# ramboard.net
KiCad netlist of a schematic drawn in EAGLE
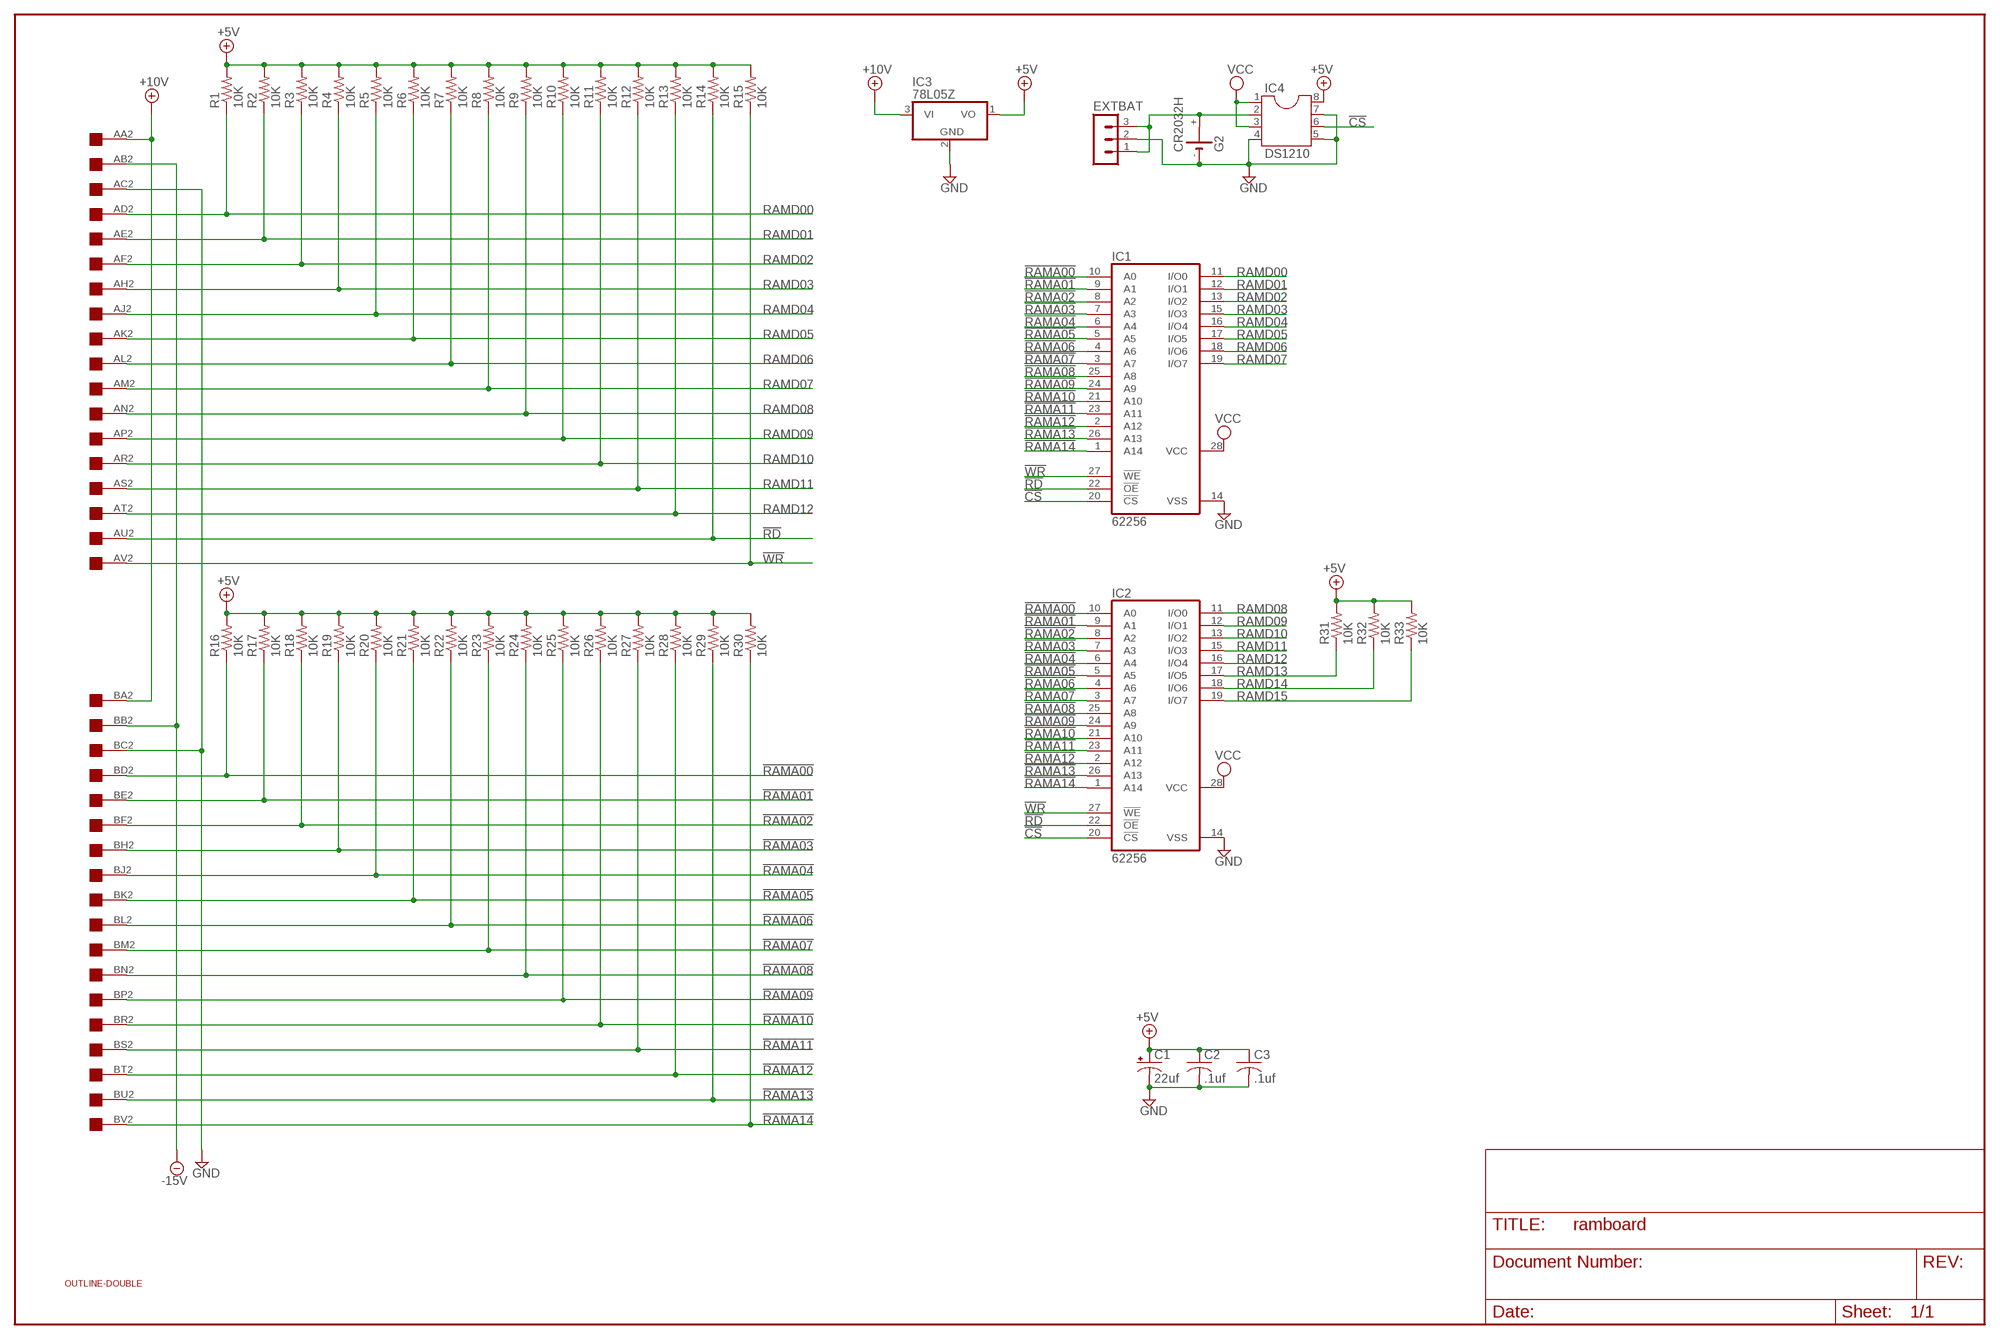
[diagram p0: schematic, sheet 1]

(export (version "E")
  (design (tool "Eeschema 10.0.6"))
  (components
    (comp (ref "C1")
      (value "22uf")
      (footprint "eagle-import:E22-6")
      (libsource (lib "eagle-import") (part "CPOL-USE22-6AXIAL"))
    )
    (comp (ref "C2")
      (value ".1uf")
      (footprint "eagle-import:C050-025X075")
      (libsource (lib "eagle-import") (part "C-US050-025X075"))
    )
    (comp (ref "C3")
      (value ".1uf")
      (footprint "eagle-import:C050-025X075")
      (libsource (lib "eagle-import") (part "C-US050-025X075"))
    )
    (comp (ref "EXTBAT")
      (value "MA03-1")
      (footprint "eagle-import:MA03-1")
      (libsource (lib "eagle-import") (part "MA03-1"))
    )
    (comp (ref "G2")
      (value "CR2032H")
      (footprint "eagle-import:CR2032H")
      (libsource (lib "eagle-import") (part "CR2032H"))
    )
    (comp (ref "IC1")
      (value "62256")
      (footprint "eagle-import:DIL28-6")
      (libsource (lib "eagle-import") (part "62256P"))
    )
    (comp (ref "IC2")
      (value "62256")
      (footprint "eagle-import:DIL28-6")
      (libsource (lib "eagle-import") (part "62256P"))
    )
    (comp (ref "IC3")
      (value "78L05Z")
      (footprint "eagle-import:TO92")
      (libsource (lib "eagle-import") (part "78ZL05"))
    )
    (comp (ref "IC4")
      (value "DS1210")
      (footprint "eagle-import:SOCKET-08")
      (libsource (lib "eagle-import") (part "DIL8S"))
    )
    (comp (ref "R1")
      (value "10K")
      (footprint "eagle-import:0207_10")
      (libsource (lib "eagle-import") (part "R-US_0207/10"))
    )
    (comp (ref "R2")
      (value "10K")
      (footprint "eagle-import:0207_10")
      (libsource (lib "eagle-import") (part "R-US_0207/10"))
    )
    (comp (ref "R3")
      (value "10K")
      (footprint "eagle-import:0207_10")
      (libsource (lib "eagle-import") (part "R-US_0207/10"))
    )
    (comp (ref "R4")
      (value "10K")
      (footprint "eagle-import:0207_10")
      (libsource (lib "eagle-import") (part "R-US_0207/10"))
    )
    (comp (ref "R5")
      (value "10K")
      (footprint "eagle-import:0207_10")
      (libsource (lib "eagle-import") (part "R-US_0207/10"))
    )
    (comp (ref "R6")
      (value "10K")
      (footprint "eagle-import:0207_10")
      (libsource (lib "eagle-import") (part "R-US_0207/10"))
    )
    (comp (ref "R7")
      (value "10K")
      (footprint "eagle-import:0207_10")
      (libsource (lib "eagle-import") (part "R-US_0207/10"))
    )
    (comp (ref "R8")
      (value "10K")
      (footprint "eagle-import:0207_10")
      (libsource (lib "eagle-import") (part "R-US_0207/10"))
    )
    (comp (ref "R9")
      (value "10K")
      (footprint "eagle-import:0207_10")
      (libsource (lib "eagle-import") (part "R-US_0207/10"))
    )
    (comp (ref "R10")
      (value "10K")
      (footprint "eagle-import:0207_10")
      (libsource (lib "eagle-import") (part "R-US_0207/10"))
    )
    (comp (ref "R11")
      (value "10K")
      (footprint "eagle-import:0207_10")
      (libsource (lib "eagle-import") (part "R-US_0207/10"))
    )
    (comp (ref "R12")
      (value "10K")
      (footprint "eagle-import:0207_10")
      (libsource (lib "eagle-import") (part "R-US_0207/10"))
    )
    (comp (ref "R13")
      (value "10K")
      (footprint "eagle-import:0207_10")
      (libsource (lib "eagle-import") (part "R-US_0207/10"))
    )
    (comp (ref "R14")
      (value "10K")
      (footprint "eagle-import:0207_10")
      (libsource (lib "eagle-import") (part "R-US_0207/10"))
    )
    (comp (ref "R15")
      (value "10K")
      (footprint "eagle-import:0207_10")
      (libsource (lib "eagle-import") (part "R-US_0207/10"))
    )
    (comp (ref "R16")
      (value "10K")
      (footprint "eagle-import:0207_10")
      (libsource (lib "eagle-import") (part "R-US_0207/10"))
    )
    (comp (ref "R17")
      (value "10K")
      (footprint "eagle-import:0207_10")
      (libsource (lib "eagle-import") (part "R-US_0207/10"))
    )
    (comp (ref "R18")
      (value "10K")
      (footprint "eagle-import:0207_10")
      (libsource (lib "eagle-import") (part "R-US_0207/10"))
    )
    (comp (ref "R19")
      (value "10K")
      (footprint "eagle-import:0207_10")
      (libsource (lib "eagle-import") (part "R-US_0207/10"))
    )
    (comp (ref "R20")
      (value "10K")
      (footprint "eagle-import:0207_10")
      (libsource (lib "eagle-import") (part "R-US_0207/10"))
    )
    (comp (ref "R21")
      (value "10K")
      (footprint "eagle-import:0207_10")
      (libsource (lib "eagle-import") (part "R-US_0207/10"))
    )
    (comp (ref "R22")
      (value "10K")
      (footprint "eagle-import:0207_10")
      (libsource (lib "eagle-import") (part "R-US_0207/10"))
    )
    (comp (ref "R23")
      (value "10K")
      (footprint "eagle-import:0207_10")
      (libsource (lib "eagle-import") (part "R-US_0207/10"))
    )
    (comp (ref "R24")
      (value "10K")
      (footprint "eagle-import:0207_10")
      (libsource (lib "eagle-import") (part "R-US_0207/10"))
    )
    (comp (ref "R25")
      (value "10K")
      (footprint "eagle-import:0207_10")
      (libsource (lib "eagle-import") (part "R-US_0207/10"))
    )
    (comp (ref "R26")
      (value "10K")
      (footprint "eagle-import:0207_10")
      (libsource (lib "eagle-import") (part "R-US_0207/10"))
    )
    (comp (ref "R27")
      (value "10K")
      (footprint "eagle-import:0207_10")
      (libsource (lib "eagle-import") (part "R-US_0207/10"))
    )
    (comp (ref "R28")
      (value "10K")
      (footprint "eagle-import:0207_10")
      (libsource (lib "eagle-import") (part "R-US_0207/10"))
    )
    (comp (ref "R29")
      (value "10K")
      (footprint "eagle-import:0207_10")
      (libsource (lib "eagle-import") (part "R-US_0207/10"))
    )
    (comp (ref "R30")
      (value "10K")
      (footprint "eagle-import:0207_10")
      (libsource (lib "eagle-import") (part "R-US_0207/10"))
    )
    (comp (ref "R31")
      (value "10K")
      (footprint "eagle-import:0207_10")
      (libsource (lib "eagle-import") (part "R-US_0207/10"))
    )
    (comp (ref "R32")
      (value "10K")
      (footprint "eagle-import:0207_10")
      (libsource (lib "eagle-import") (part "R-US_0207/10"))
    )
    (comp (ref "R33")
      (value "10K")
      (footprint "eagle-import:0207_10")
      (libsource (lib "eagle-import") (part "R-US_0207/10"))
    )
    (comp (ref "U$1")
      (value "OUTLINE-DOUBLE")
      (footprint "eagle-import:DOUBLE")
      (libsource (lib "eagle-import") (part "OUTLINE-DOUBLE"))
    )
    (comp (ref "U$2")
      (value "DOUBLE")
      (footprint "eagle-import:EDGE-CON4")
      (libsource (lib "eagle-import") (part "DOUBLE"))
    )
  )
  (nets
    (net (code "1") (name "+5V") (class "Default")
      (node (ref "C1") (pin "+") (pinfunction "+_+") (pintype "passive"))
      (node (ref "C2") (pin "1") (pinfunction "1_1") (pintype "passive"))
      (node (ref "C3") (pin "1") (pinfunction "1_1") (pintype "passive"))
      (node (ref "IC3") (pin "1") (pinfunction "VO_1") (pintype "passive"))
      (node (ref "IC4") (pin "8") (pinfunction "8_8") (pintype "passive"))
      (node (ref "R1") (pin "2") (pinfunction "2_2") (pintype "passive"))
      (node (ref "R10") (pin "2") (pinfunction "2_2") (pintype "passive"))
      (node (ref "R11") (pin "2") (pinfunction "2_2") (pintype "passive"))
      (node (ref "R12") (pin "2") (pinfunction "2_2") (pintype "passive"))
      (node (ref "R13") (pin "2") (pinfunction "2_2") (pintype "passive"))
      (node (ref "R14") (pin "2") (pinfunction "2_2") (pintype "passive"))
      (node (ref "R15") (pin "2") (pinfunction "2_2") (pintype "passive"))
      (node (ref "R16") (pin "2") (pinfunction "2_2") (pintype "passive"))
      (node (ref "R17") (pin "2") (pinfunction "2_2") (pintype "passive"))
      (node (ref "R18") (pin "2") (pinfunction "2_2") (pintype "passive"))
      (node (ref "R19") (pin "2") (pinfunction "2_2") (pintype "passive"))
      (node (ref "R2") (pin "2") (pinfunction "2_2") (pintype "passive"))
      (node (ref "R20") (pin "2") (pinfunction "2_2") (pintype "passive"))
      (node (ref "R21") (pin "2") (pinfunction "2_2") (pintype "passive"))
      (node (ref "R22") (pin "2") (pinfunction "2_2") (pintype "passive"))
      (node (ref "R23") (pin "2") (pinfunction "2_2") (pintype "passive"))
      (node (ref "R24") (pin "2") (pinfunction "2_2") (pintype "passive"))
      (node (ref "R25") (pin "2") (pinfunction "2_2") (pintype "passive"))
      (node (ref "R26") (pin "2") (pinfunction "2_2") (pintype "passive"))
      (node (ref "R27") (pin "2") (pinfunction "2_2") (pintype "passive"))
      (node (ref "R28") (pin "2") (pinfunction "2_2") (pintype "passive"))
      (node (ref "R29") (pin "2") (pinfunction "2_2") (pintype "passive"))
      (node (ref "R3") (pin "2") (pinfunction "2_2") (pintype "passive"))
      (node (ref "R30") (pin "2") (pinfunction "2_2") (pintype "passive"))
      (node (ref "R31") (pin "2") (pinfunction "2_2") (pintype "passive"))
      (node (ref "R32") (pin "2") (pinfunction "2_2") (pintype "passive"))
      (node (ref "R33") (pin "2") (pinfunction "2_2") (pintype "passive"))
      (node (ref "R4") (pin "2") (pinfunction "2_2") (pintype "passive"))
      (node (ref "R5") (pin "2") (pinfunction "2_2") (pintype "passive"))
      (node (ref "R6") (pin "2") (pinfunction "2_2") (pintype "passive"))
      (node (ref "R7") (pin "2") (pinfunction "2_2") (pintype "passive"))
      (node (ref "R8") (pin "2") (pinfunction "2_2") (pintype "passive"))
      (node (ref "R9") (pin "2") (pinfunction "2_2") (pintype "passive"))
    )
    (net (code "2") (name "+10V") (class "Default")
      (node (ref "IC3") (pin "3") (pinfunction "VI_3") (pintype "input"))
      (node (ref "U$2") (pin "AA2") (pinfunction "1_AA2") (pintype "bidirectional"))
      (node (ref "U$2") (pin "BA2") (pinfunction "1_BA2") (pintype "bidirectional"))
    )
    (net (code "3") (name "-15V") (class "Default")
      (node (ref "U$2") (pin "AB2") (pinfunction "1_AB2") (pintype "bidirectional"))
      (node (ref "U$2") (pin "BB2") (pinfunction "1_BB2") (pintype "bidirectional"))
    )
    (net (code "4") (name "/RAMD00") (class "Default")
      (node (ref "IC1") (pin "11") (pinfunction "I/O0_11") (pintype "bidirectional"))
      (node (ref "R1") (pin "1") (pinfunction "1_1") (pintype "passive"))
      (node (ref "U$2") (pin "AD2") (pinfunction "1_AD2") (pintype "bidirectional"))
    )
    (net (code "5") (name "/RAMD01") (class "Default")
      (node (ref "IC1") (pin "12") (pinfunction "I/O1_12") (pintype "bidirectional"))
      (node (ref "R2") (pin "1") (pinfunction "1_1") (pintype "passive"))
      (node (ref "U$2") (pin "AE2") (pinfunction "1_AE2") (pintype "bidirectional"))
    )
    (net (code "6") (name "/RAMD02") (class "Default")
      (node (ref "IC1") (pin "13") (pinfunction "I/O2_13") (pintype "bidirectional"))
      (node (ref "R3") (pin "1") (pinfunction "1_1") (pintype "passive"))
      (node (ref "U$2") (pin "AF2") (pinfunction "1_AF2") (pintype "bidirectional"))
    )
    (net (code "7") (name "/RAMD03") (class "Default")
      (node (ref "IC1") (pin "15") (pinfunction "I/O3_15") (pintype "bidirectional"))
      (node (ref "R4") (pin "1") (pinfunction "1_1") (pintype "passive"))
      (node (ref "U$2") (pin "AH2") (pinfunction "1_AH2") (pintype "bidirectional"))
    )
    (net (code "8") (name "/RAMD04") (class "Default")
      (node (ref "IC1") (pin "16") (pinfunction "I/O4_16") (pintype "bidirectional"))
      (node (ref "R5") (pin "1") (pinfunction "1_1") (pintype "passive"))
      (node (ref "U$2") (pin "AJ2") (pinfunction "1_AJ2") (pintype "bidirectional"))
    )
    (net (code "9") (name "/RAMD05") (class "Default")
      (node (ref "IC1") (pin "17") (pinfunction "I/O5_17") (pintype "bidirectional"))
      (node (ref "R6") (pin "1") (pinfunction "1_1") (pintype "passive"))
      (node (ref "U$2") (pin "AK2") (pinfunction "1_AK2") (pintype "bidirectional"))
    )
    (net (code "10") (name "/RAMD06") (class "Default")
      (node (ref "IC1") (pin "18") (pinfunction "I/O6_18") (pintype "bidirectional"))
      (node (ref "R7") (pin "1") (pinfunction "1_1") (pintype "passive"))
      (node (ref "U$2") (pin "AL2") (pinfunction "1_AL2") (pintype "bidirectional"))
    )
    (net (code "11") (name "/RAMD07") (class "Default")
      (node (ref "IC1") (pin "19") (pinfunction "I/O7_19") (pintype "bidirectional"))
      (node (ref "R8") (pin "1") (pinfunction "1_1") (pintype "passive"))
      (node (ref "U$2") (pin "AM2") (pinfunction "1_AM2") (pintype "bidirectional"))
    )
    (net (code "12") (name "/RAMD08") (class "Default")
      (node (ref "IC2") (pin "11") (pinfunction "I/O0_11") (pintype "bidirectional"))
      (node (ref "R9") (pin "1") (pinfunction "1_1") (pintype "passive"))
      (node (ref "U$2") (pin "AN2") (pinfunction "1_AN2") (pintype "bidirectional"))
    )
    (net (code "13") (name "/RAMD09") (class "Default")
      (node (ref "IC2") (pin "12") (pinfunction "I/O1_12") (pintype "bidirectional"))
      (node (ref "R10") (pin "1") (pinfunction "1_1") (pintype "passive"))
      (node (ref "U$2") (pin "AP2") (pinfunction "1_AP2") (pintype "bidirectional"))
    )
    (net (code "14") (name "/RAMD10") (class "Default")
      (node (ref "IC2") (pin "13") (pinfunction "I/O2_13") (pintype "bidirectional"))
      (node (ref "R11") (pin "1") (pinfunction "1_1") (pintype "passive"))
      (node (ref "U$2") (pin "AR2") (pinfunction "1_AR2") (pintype "bidirectional"))
    )
    (net (code "15") (name "/RAMD11") (class "Default")
      (node (ref "IC2") (pin "15") (pinfunction "I/O3_15") (pintype "bidirectional"))
      (node (ref "R12") (pin "1") (pinfunction "1_1") (pintype "passive"))
      (node (ref "U$2") (pin "AS2") (pinfunction "1_AS2") (pintype "bidirectional"))
    )
    (net (code "16") (name "/RAMD12") (class "Default")
      (node (ref "IC2") (pin "16") (pinfunction "I/O4_16") (pintype "bidirectional"))
      (node (ref "R13") (pin "1") (pinfunction "1_1") (pintype "passive"))
      (node (ref "U$2") (pin "AT2") (pinfunction "1_AT2") (pintype "bidirectional"))
    )
    (net (code "17") (name "/RAMD13") (class "Default")
      (node (ref "IC2") (pin "17") (pinfunction "I/O5_17") (pintype "bidirectional"))
      (node (ref "R31") (pin "1") (pinfunction "1_1") (pintype "passive"))
    )
    (net (code "18") (name "/RAMD14") (class "Default")
      (node (ref "IC2") (pin "18") (pinfunction "I/O6_18") (pintype "bidirectional"))
      (node (ref "R32") (pin "1") (pinfunction "1_1") (pintype "passive"))
    )
    (net (code "19") (name "/RAMD15") (class "Default")
      (node (ref "IC2") (pin "19") (pinfunction "I/O7_19") (pintype "bidirectional"))
      (node (ref "R33") (pin "1") (pinfunction "1_1") (pintype "passive"))
    )
    (net (code "20") (name "/~{CS}") (class "Default")
      (node (ref "IC1") (pin "20") (pinfunction "~{CS}_20") (pintype "input"))
      (node (ref "IC2") (pin "20") (pinfunction "~{CS}_20") (pintype "input"))
      (node (ref "IC4") (pin "6") (pinfunction "6_6") (pintype "passive"))
    )
    (net (code "21") (name "/~{RAMA00}") (class "Default")
      (node (ref "IC1") (pin "10") (pinfunction "A0_10") (pintype "input"))
      (node (ref "IC2") (pin "10") (pinfunction "A0_10") (pintype "input"))
      (node (ref "R16") (pin "1") (pinfunction "1_1") (pintype "passive"))
      (node (ref "U$2") (pin "BD2") (pinfunction "1_BD2") (pintype "bidirectional"))
    )
    (net (code "22") (name "/~{RAMA01}") (class "Default")
      (node (ref "IC1") (pin "9") (pinfunction "A1_9") (pintype "input"))
      (node (ref "IC2") (pin "9") (pinfunction "A1_9") (pintype "input"))
      (node (ref "R17") (pin "1") (pinfunction "1_1") (pintype "passive"))
      (node (ref "U$2") (pin "BE2") (pinfunction "1_BE2") (pintype "bidirectional"))
    )
    (net (code "23") (name "/~{RAMA02}") (class "Default")
      (node (ref "IC1") (pin "8") (pinfunction "A2_8") (pintype "input"))
      (node (ref "IC2") (pin "8") (pinfunction "A2_8") (pintype "input"))
      (node (ref "R18") (pin "1") (pinfunction "1_1") (pintype "passive"))
      (node (ref "U$2") (pin "BF2") (pinfunction "1_BF2") (pintype "bidirectional"))
    )
    (net (code "24") (name "/~{RAMA03}") (class "Default")
      (node (ref "IC1") (pin "7") (pinfunction "A3_7") (pintype "input"))
      (node (ref "IC2") (pin "7") (pinfunction "A3_7") (pintype "input"))
      (node (ref "R19") (pin "1") (pinfunction "1_1") (pintype "passive"))
      (node (ref "U$2") (pin "BH2") (pinfunction "1_BH2") (pintype "bidirectional"))
    )
    (net (code "25") (name "/~{RAMA04}") (class "Default")
      (node (ref "IC1") (pin "6") (pinfunction "A4_6") (pintype "input"))
      (node (ref "IC2") (pin "6") (pinfunction "A4_6") (pintype "input"))
      (node (ref "R20") (pin "1") (pinfunction "1_1") (pintype "passive"))
      (node (ref "U$2") (pin "BJ2") (pinfunction "1_BJ2") (pintype "bidirectional"))
    )
    (net (code "26") (name "/~{RAMA05}") (class "Default")
      (node (ref "IC1") (pin "5") (pinfunction "A5_5") (pintype "input"))
      (node (ref "IC2") (pin "5") (pinfunction "A5_5") (pintype "input"))
      (node (ref "R21") (pin "1") (pinfunction "1_1") (pintype "passive"))
      (node (ref "U$2") (pin "BK2") (pinfunction "1_BK2") (pintype "bidirectional"))
    )
    (net (code "27") (name "/~{RAMA06}") (class "Default")
      (node (ref "IC1") (pin "4") (pinfunction "A6_4") (pintype "input"))
      (node (ref "IC2") (pin "4") (pinfunction "A6_4") (pintype "input"))
      (node (ref "R22") (pin "1") (pinfunction "1_1") (pintype "passive"))
      (node (ref "U$2") (pin "BL2") (pinfunction "1_BL2") (pintype "bidirectional"))
    )
    (net (code "28") (name "/~{RAMA07}") (class "Default")
      (node (ref "IC1") (pin "3") (pinfunction "A7_3") (pintype "input"))
      (node (ref "IC2") (pin "3") (pinfunction "A7_3") (pintype "input"))
      (node (ref "R23") (pin "1") (pinfunction "1_1") (pintype "passive"))
      (node (ref "U$2") (pin "BM2") (pinfunction "1_BM2") (pintype "bidirectional"))
    )
    (net (code "29") (name "/~{RAMA08}") (class "Default")
      (node (ref "IC1") (pin "25") (pinfunction "A8_25") (pintype "input"))
      (node (ref "IC2") (pin "25") (pinfunction "A8_25") (pintype "input"))
      (node (ref "R24") (pin "1") (pinfunction "1_1") (pintype "passive"))
      (node (ref "U$2") (pin "BN2") (pinfunction "1_BN2") (pintype "bidirectional"))
    )
    (net (code "30") (name "/~{RAMA09}") (class "Default")
      (node (ref "IC1") (pin "24") (pinfunction "A9_24") (pintype "input"))
      (node (ref "IC2") (pin "24") (pinfunction "A9_24") (pintype "input"))
      (node (ref "R25") (pin "1") (pinfunction "1_1") (pintype "passive"))
      (node (ref "U$2") (pin "BP2") (pinfunction "1_BP2") (pintype "bidirectional"))
    )
    (net (code "31") (name "/~{RAMA10}") (class "Default")
      (node (ref "IC1") (pin "21") (pinfunction "A10_21") (pintype "input"))
      (node (ref "IC2") (pin "21") (pinfunction "A10_21") (pintype "input"))
      (node (ref "R26") (pin "1") (pinfunction "1_1") (pintype "passive"))
      (node (ref "U$2") (pin "BR2") (pinfunction "1_BR2") (pintype "bidirectional"))
    )
    (net (code "32") (name "/~{RAMA11}") (class "Default")
      (node (ref "IC1") (pin "23") (pinfunction "A11_23") (pintype "input"))
      (node (ref "IC2") (pin "23") (pinfunction "A11_23") (pintype "input"))
      (node (ref "R27") (pin "1") (pinfunction "1_1") (pintype "passive"))
      (node (ref "U$2") (pin "BS2") (pinfunction "1_BS2") (pintype "bidirectional"))
    )
    (net (code "33") (name "/~{RAMA12}") (class "Default")
      (node (ref "IC1") (pin "2") (pinfunction "A12_2") (pintype "input"))
      (node (ref "IC2") (pin "2") (pinfunction "A12_2") (pintype "input"))
      (node (ref "R28") (pin "1") (pinfunction "1_1") (pintype "passive"))
      (node (ref "U$2") (pin "BT2") (pinfunction "1_BT2") (pintype "bidirectional"))
    )
    (net (code "34") (name "/~{RAMA13}") (class "Default")
      (node (ref "IC1") (pin "26") (pinfunction "A13_26") (pintype "input"))
      (node (ref "IC2") (pin "26") (pinfunction "A13_26") (pintype "input"))
      (node (ref "R29") (pin "1") (pinfunction "1_1") (pintype "passive"))
      (node (ref "U$2") (pin "BU2") (pinfunction "1_BU2") (pintype "bidirectional"))
    )
    (net (code "35") (name "/~{RAMA14}") (class "Default")
      (node (ref "IC1") (pin "1") (pinfunction "A14_1") (pintype "input"))
      (node (ref "IC2") (pin "1") (pinfunction "A14_1") (pintype "input"))
      (node (ref "R30") (pin "1") (pinfunction "1_1") (pintype "passive"))
      (node (ref "U$2") (pin "BV2") (pinfunction "1_BV2") (pintype "bidirectional"))
    )
    (net (code "36") (name "/~{RD}") (class "Default")
      (node (ref "IC1") (pin "22") (pinfunction "~{OE}_22") (pintype "input"))
      (node (ref "IC2") (pin "22") (pinfunction "~{OE}_22") (pintype "input"))
      (node (ref "R14") (pin "1") (pinfunction "1_1") (pintype "passive"))
      (node (ref "U$2") (pin "AU2") (pinfunction "1_AU2") (pintype "bidirectional"))
    )
    (net (code "37") (name "/~{WR}") (class "Default")
      (node (ref "IC1") (pin "27") (pinfunction "~{WE}_27") (pintype "input"))
      (node (ref "IC2") (pin "27") (pinfunction "~{WE}_27") (pintype "input"))
      (node (ref "R15") (pin "1") (pinfunction "1_1") (pintype "passive"))
      (node (ref "U$2") (pin "AV2") (pinfunction "1_AV2") (pintype "bidirectional"))
    )
    (net (code "38") (name "GND") (class "Default")
      (node (ref "C1") (pin "-") (pinfunction "-_-") (pintype "passive"))
      (node (ref "C2") (pin "2") (pinfunction "2_2") (pintype "passive"))
      (node (ref "C3") (pin "2") (pinfunction "2_2") (pintype "passive"))
      (node (ref "EXTBAT") (pin "2") (pinfunction "2_2") (pintype "passive"))
      (node (ref "G2") (pin "-") (pinfunction "-_-") (pintype "passive"))
      (node (ref "IC1") (pin "14") (pinfunction "VSS_14") (pintype "power_in"))
      (node (ref "IC2") (pin "14") (pinfunction "VSS_14") (pintype "power_in"))
      (node (ref "IC3") (pin "2") (pinfunction "GND_2") (pintype "passive"))
      (node (ref "IC4") (pin "4") (pinfunction "4_4") (pintype "passive"))
      (node (ref "IC4") (pin "5") (pinfunction "5_5") (pintype "passive"))
      (node (ref "IC4") (pin "7") (pinfunction "7_7") (pintype "passive"))
      (node (ref "U$2") (pin "AC2") (pinfunction "1_AC2") (pintype "bidirectional"))
      (node (ref "U$2") (pin "BC2") (pinfunction "1_BC2") (pintype "bidirectional"))
    )
    (net (code "39") (name "Net-(EXTBAT-Pad1)") (class "Default")
      (node (ref "EXTBAT") (pin "1") (pinfunction "1_1") (pintype "passive"))
      (node (ref "EXTBAT") (pin "3") (pinfunction "3_3") (pintype "passive"))
      (node (ref "G2") (pin "+") (pinfunction "+_+") (pintype "passive"))
      (node (ref "IC4") (pin "2") (pinfunction "2_2") (pintype "passive"))
    )
    (net (code "40") (name "VCC") (class "Default")
      (node (ref "IC1") (pin "28") (pinfunction "VCC_28") (pintype "power_in"))
      (node (ref "IC2") (pin "28") (pinfunction "VCC_28") (pintype "power_in"))
      (node (ref "IC4") (pin "1") (pinfunction "1_1") (pintype "passive"))
      (node (ref "IC4") (pin "3") (pinfunction "3_3") (pintype "passive"))
    )
    (net (code "41") (name "unconnected-(G2-+-Pad+@1)") (class "Default")
      (node (ref "G2") (pin "+@1") (pinfunction "+_+@1") (pintype "passive"))
    )
  )
)
